# second.net
KiCad netlist of a schematic drawn in EAGLE
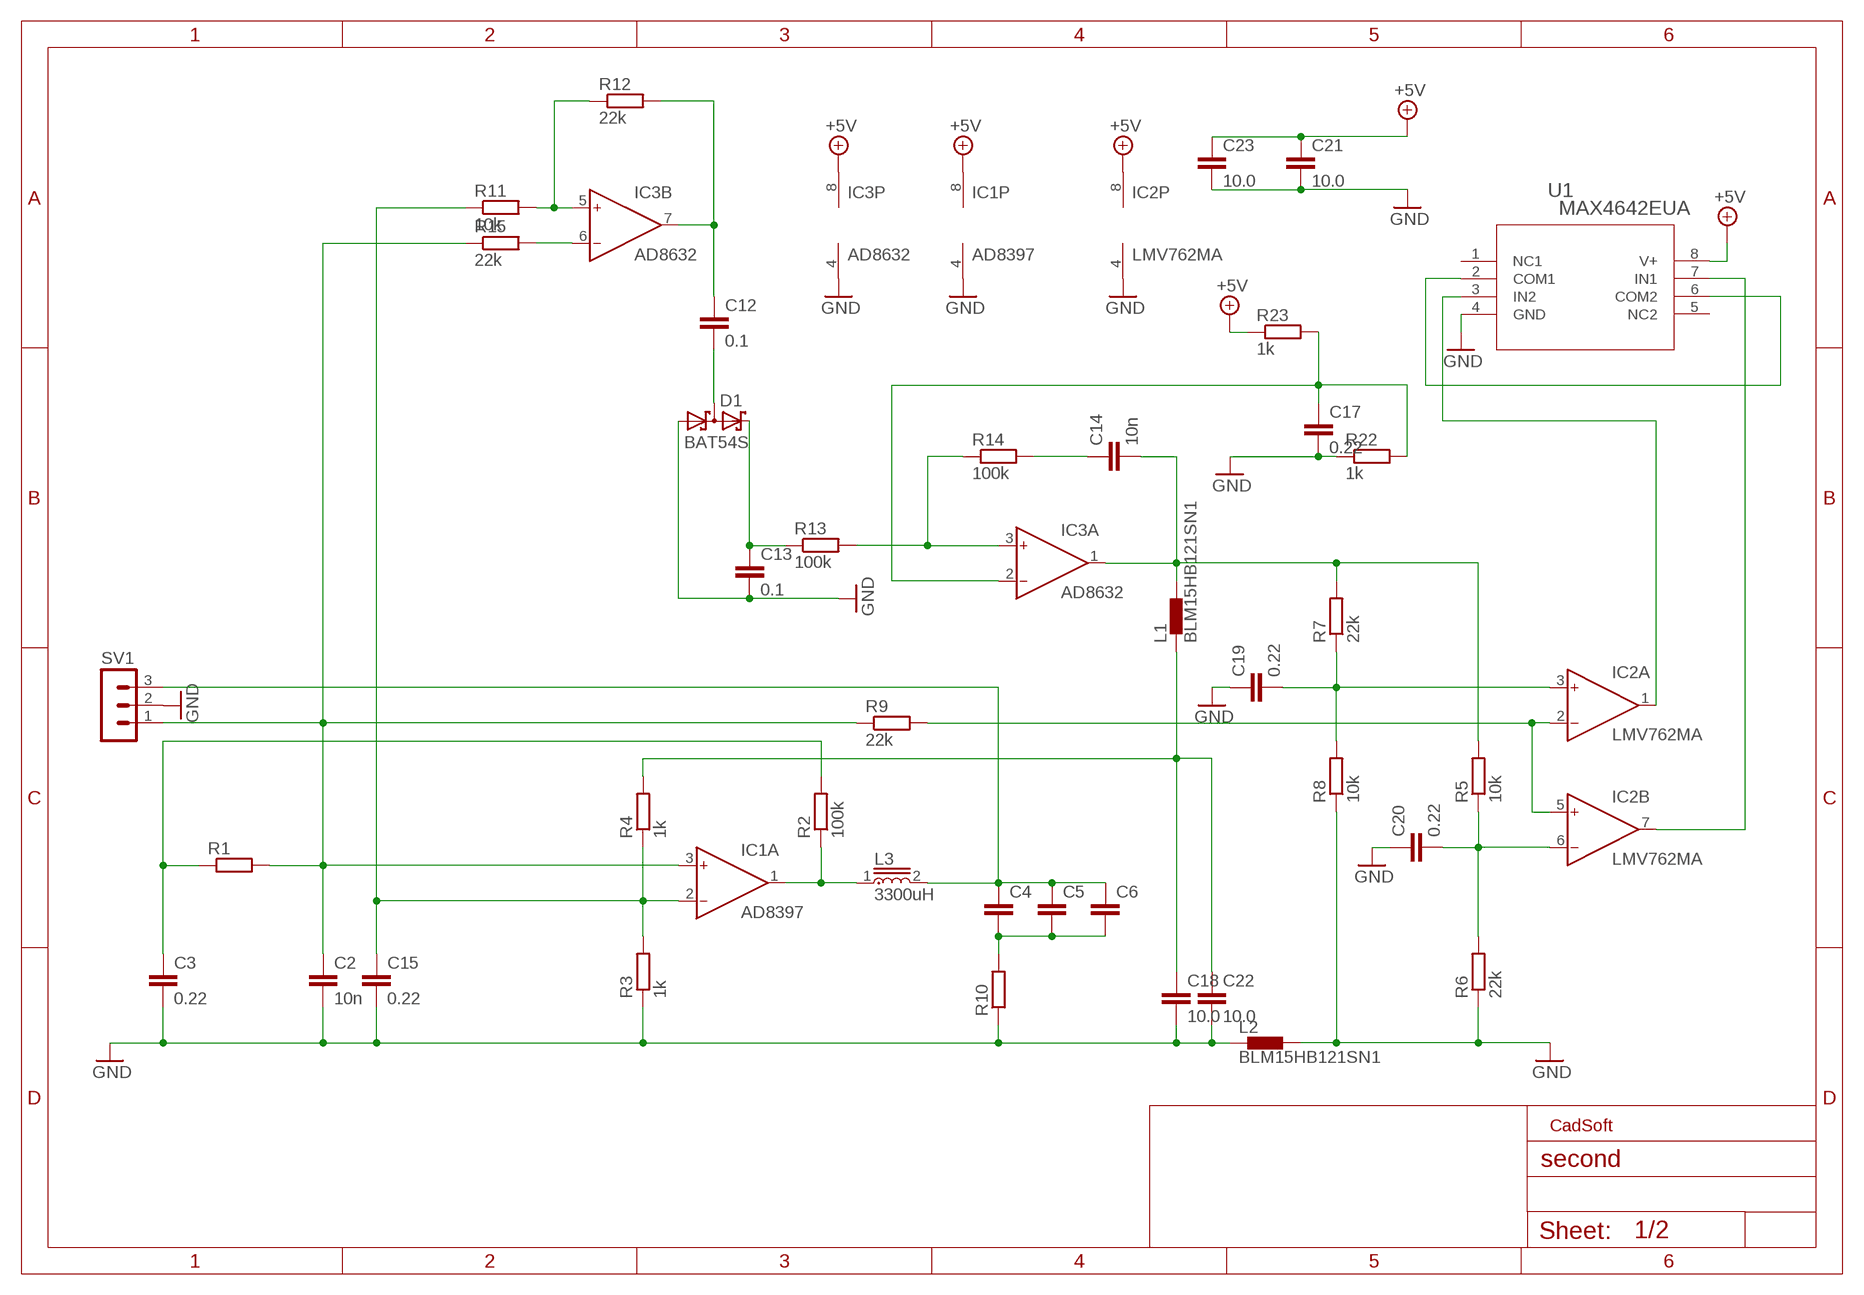
[diagram p0: schematic, sheet 1]
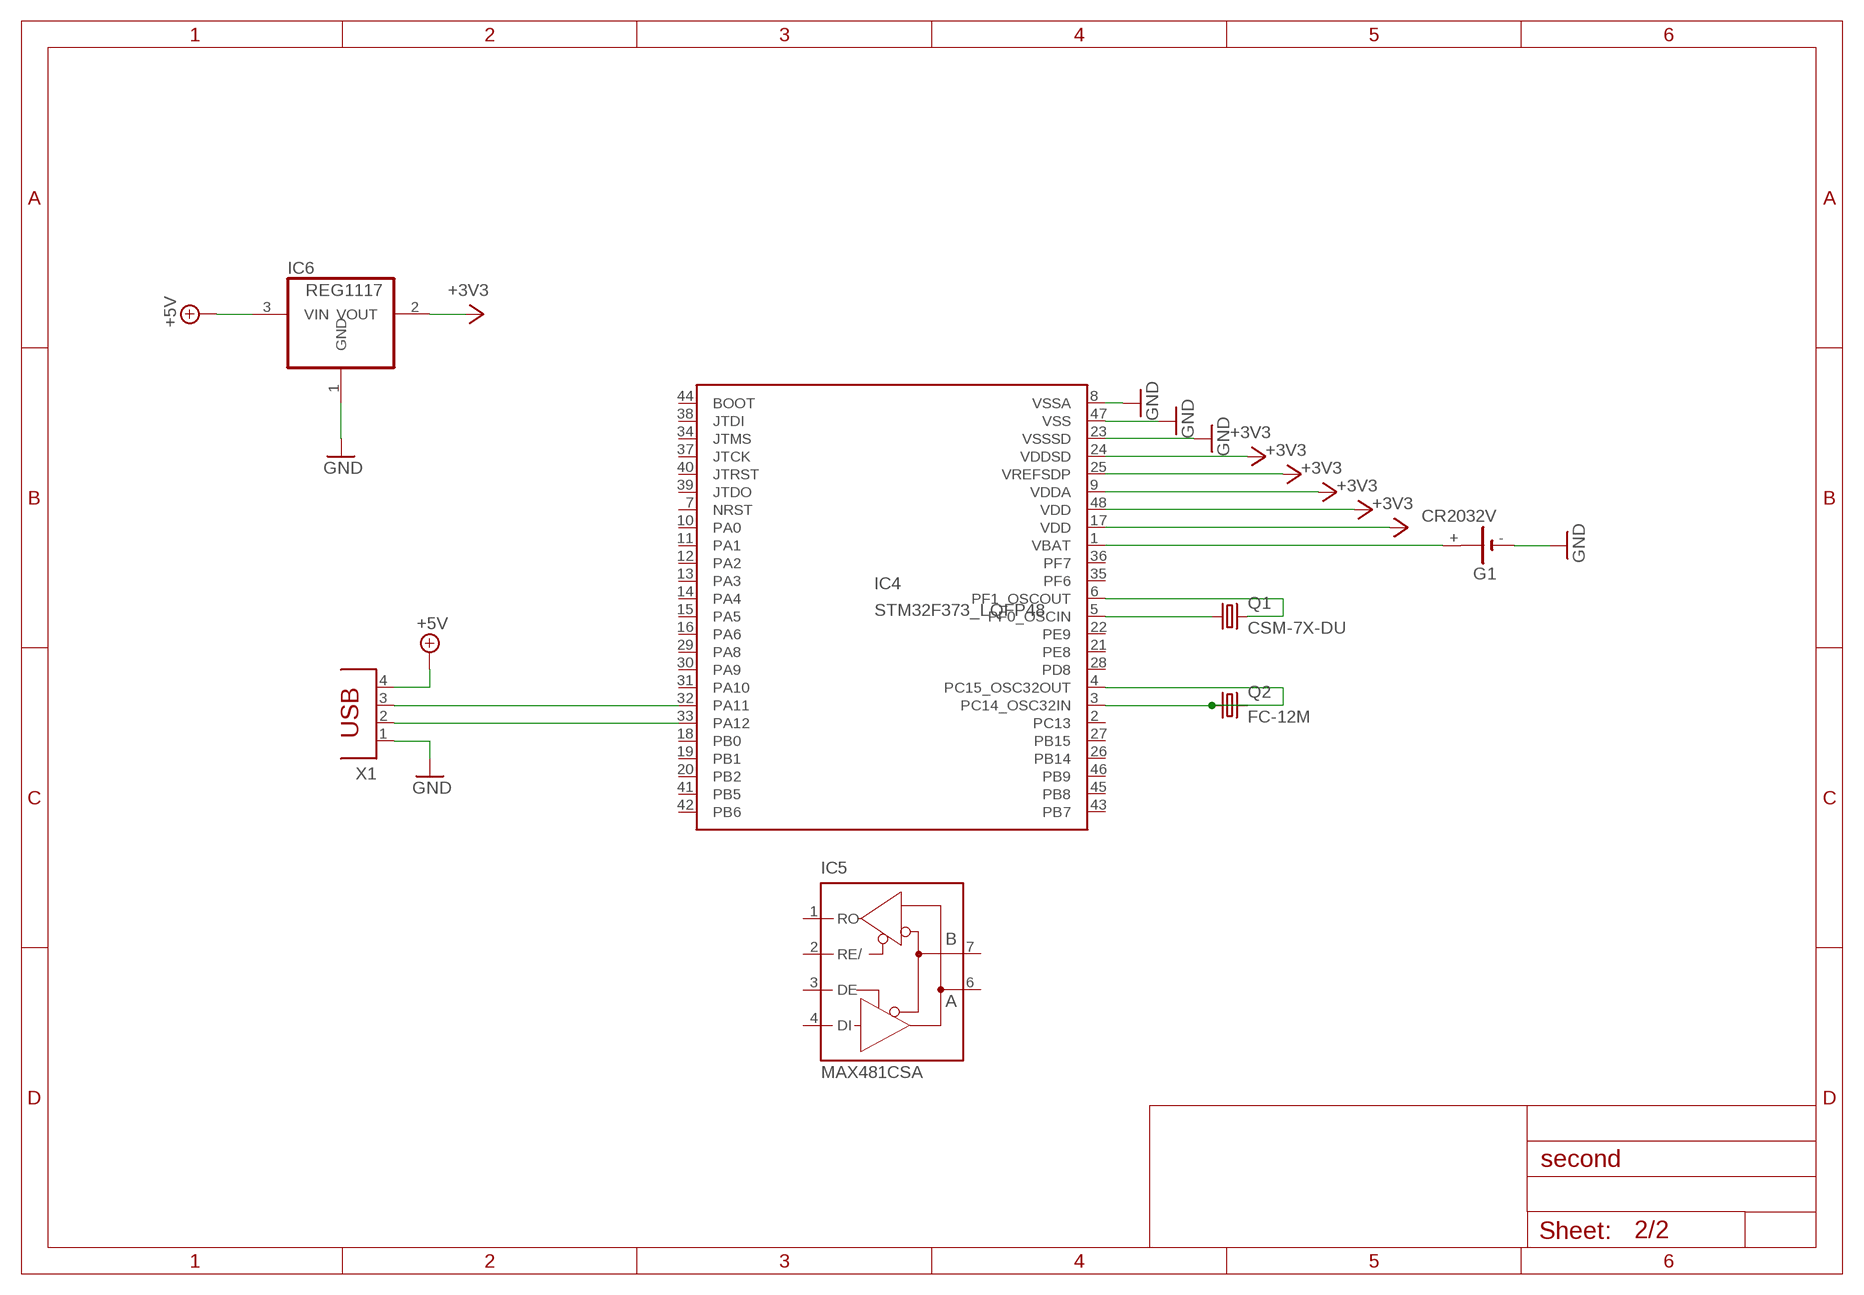
[diagram p1: schematic, sheet 2]

(export (version "E")
  (design (tool "Eeschema 10.0.6"))
  (components
    (comp (ref "C2")
      (value "10n")
      (footprint "eagle-import:C0805")
      (libsource (lib "eagle-import") (part "C-EUC0805"))
    )
    (comp (ref "C3")
      (value "0.22")
      (footprint "eagle-import:C0805")
      (libsource (lib "eagle-import") (part "C-EUC0805"))
    )
    (comp (ref "C4")
      (value "C-EUC0805")
      (footprint "eagle-import:C0805")
      (libsource (lib "eagle-import") (part "C-EUC0805"))
    )
    (comp (ref "C5")
      (value "C-EUC0805")
      (footprint "eagle-import:C0805")
      (libsource (lib "eagle-import") (part "C-EUC0805"))
    )
    (comp (ref "C6")
      (value "C-EUC0805")
      (footprint "eagle-import:C0805")
      (libsource (lib "eagle-import") (part "C-EUC0805"))
    )
    (comp (ref "C12")
      (value "0.1")
      (footprint "eagle-import:C0805")
      (libsource (lib "eagle-import") (part "C-EUC0805"))
    )
    (comp (ref "C13")
      (value "0.1")
      (footprint "eagle-import:C0805")
      (libsource (lib "eagle-import") (part "C-EUC0805"))
    )
    (comp (ref "C14")
      (value "10n")
      (footprint "eagle-import:C0805")
      (libsource (lib "eagle-import") (part "C-EUC0805"))
    )
    (comp (ref "C15")
      (value "0.22")
      (footprint "eagle-import:C0805")
      (libsource (lib "eagle-import") (part "C-EUC0805"))
    )
    (comp (ref "C17")
      (value "0.22")
      (footprint "eagle-import:C0805")
      (libsource (lib "eagle-import") (part "C-EUC0805"))
    )
    (comp (ref "C18")
      (value "10.0")
      (footprint "eagle-import:C0805")
      (libsource (lib "eagle-import") (part "C-EUC0805"))
    )
    (comp (ref "C19")
      (value "0.22")
      (footprint "eagle-import:C0805")
      (libsource (lib "eagle-import") (part "C-EUC0805"))
    )
    (comp (ref "C20")
      (value "0.22")
      (footprint "eagle-import:C0805")
      (libsource (lib "eagle-import") (part "C-EUC0805"))
    )
    (comp (ref "C21")
      (value "10.0")
      (footprint "eagle-import:C0805")
      (libsource (lib "eagle-import") (part "C-EUC0805"))
    )
    (comp (ref "C22")
      (value "10.0")
      (footprint "eagle-import:C0805")
      (libsource (lib "eagle-import") (part "C-EUC0805"))
    )
    (comp (ref "C23")
      (value "10.0")
      (footprint "eagle-import:C0805")
      (libsource (lib "eagle-import") (part "C-EUC0805"))
    )
    (comp (ref "D1")
      (value "BAT54S")
      (footprint "eagle-import:SOT23")
      (libsource (lib "eagle-import") (part "BAT54S"))
    )
    (comp (ref "IC1")
      (value "AD8397")
      (footprint "eagle-import:SO8")
      (fields (field (name "MF") "ANALOG DEVICES") (field (name "MPN") "AD822BRZ"))
      (libsource (lib "eagle-import") (part "AD822R"))
    )
    (comp (ref "IC2")
      (value "LMV762MA")
      (footprint "eagle-import:SO8")
      (fields (field (name "MF") "ANALOG DEVICES") (field (name "MPN") "AD822BRZ"))
      (libsource (lib "eagle-import") (part "AD822R"))
    )
    (comp (ref "IC3")
      (value "AD8632")
      (footprint "eagle-import:SO8")
      (fields (field (name "MF") "ANALOG DEVICES") (field (name "MPN") "AD822BRZ"))
      (libsource (lib "eagle-import") (part "AD822R"))
    )
    (comp (ref "L1")
      (value "BLM15HB121SN1")
      (footprint "eagle-import:0402")
      (libsource (lib "eagle-import") (part "BLM15HB121SN1"))
    )
    (comp (ref "L2")
      (value "BLM15HB121SN1")
      (footprint "eagle-import:0402")
      (libsource (lib "eagle-import") (part "BLM15HB121SN1"))
    )
    (comp (ref "L3")
      (value "3300uH")
      (footprint "eagle-import:P0762NL")
      (libsource (lib "eagle-import") (part "P0762.NL103"))
    )
    (comp (ref "R1")
      (value "R-EU_R0805")
      (footprint "eagle-import:R0805")
      (libsource (lib "eagle-import") (part "R-EU_R0805"))
    )
    (comp (ref "R2")
      (value "100k")
      (footprint "eagle-import:R0805")
      (libsource (lib "eagle-import") (part "R-EU_R0805"))
    )
    (comp (ref "R3")
      (value "1k")
      (footprint "eagle-import:R0805")
      (libsource (lib "eagle-import") (part "R-EU_R0805"))
    )
    (comp (ref "R4")
      (value "1k")
      (footprint "eagle-import:R0805")
      (libsource (lib "eagle-import") (part "R-EU_R0805"))
    )
    (comp (ref "R5")
      (value "10k")
      (footprint "eagle-import:R0805")
      (libsource (lib "eagle-import") (part "R-EU_R0805"))
    )
    (comp (ref "R6")
      (value "22k")
      (footprint "eagle-import:R0805")
      (libsource (lib "eagle-import") (part "R-EU_R0805"))
    )
    (comp (ref "R7")
      (value "22k")
      (footprint "eagle-import:R0805")
      (libsource (lib "eagle-import") (part "R-EU_R0805"))
    )
    (comp (ref "R8")
      (value "10k")
      (footprint "eagle-import:R0805")
      (libsource (lib "eagle-import") (part "R-EU_R0805"))
    )
    (comp (ref "R9")
      (value "22k")
      (footprint "eagle-import:R0805")
      (libsource (lib "eagle-import") (part "R-EU_R0805"))
    )
    (comp (ref "R10")
      (value "R-EU_R0805")
      (footprint "eagle-import:R0805")
      (libsource (lib "eagle-import") (part "R-EU_R0805"))
    )
    (comp (ref "R11")
      (value "10k")
      (footprint "eagle-import:R0805")
      (libsource (lib "eagle-import") (part "R-EU_R0805"))
    )
    (comp (ref "R12")
      (value "22k")
      (footprint "eagle-import:R0805")
      (libsource (lib "eagle-import") (part "R-EU_R0805"))
    )
    (comp (ref "R13")
      (value "100k")
      (footprint "eagle-import:R0805")
      (libsource (lib "eagle-import") (part "R-EU_R0805"))
    )
    (comp (ref "R14")
      (value "100k")
      (footprint "eagle-import:R0805")
      (libsource (lib "eagle-import") (part "R-EU_R0805"))
    )
    (comp (ref "R15")
      (value "22k")
      (footprint "eagle-import:R0805")
      (libsource (lib "eagle-import") (part "R-EU_R0805"))
    )
    (comp (ref "R22")
      (value "1k")
      (footprint "eagle-import:R0805")
      (libsource (lib "eagle-import") (part "R-EU_R0805"))
    )
    (comp (ref "R23")
      (value "1k")
      (footprint "eagle-import:R0805")
      (libsource (lib "eagle-import") (part "R-EU_R0805"))
    )
    (comp (ref "SV1")
      (value "MA03-1")
      (footprint "eagle-import:MA03-1")
      (libsource (lib "eagle-import") (part "MA03-1"))
    )
    (comp (ref "U1")
      (value "MAX4642EUA")
      (footprint "eagle-import:21-0036K")
      (fields (field (name "MANUFACTURER_PART_NUMBER") "max4642eua"))
      (libsource (lib "eagle-import") (part "MAX4642EUA"))
    )
    (comp (ref "G1")
      (value "CR2032V")
      (footprint "eagle-import:CR2032V")
      (libsource (lib "eagle-import") (part "CR2032V"))
    )
    (comp (ref "IC4")
      (value "STM32F373_LQFP48")
      (footprint "eagle-import:LQFP48_PACKAGE")
      (libsource (lib "eagle-import") (part "STM32F373_LQFP48"))
    )
    (comp (ref "IC5")
      (value "MAX481CSA")
      (footprint "eagle-import:SO08")
      (fields (field (name "MF") "MAXIM"))
      (libsource (lib "eagle-import") (part "MAX481CSA"))
    )
    (comp (ref "IC6")
      (value "REG1117")
      (footprint "eagle-import:SOT223")
      (libsource (lib "eagle-import") (part "REG1117"))
    )
    (comp (ref "Q1")
      (value "CSM-7X-DU")
      (footprint "eagle-import:CSM-7X-DU")
      (libsource (lib "eagle-import") (part "CSM-7X-DU"))
    )
    (comp (ref "Q2")
      (value "FC-12M")
      (footprint "eagle-import:FC-12M")
      (libsource (lib "eagle-import") (part "FC-12M"))
    )
    (comp (ref "X1")
      (value "PN61729")
      (footprint "eagle-import:PN61729")
      (libsource (lib "eagle-import") (part "PN61729"))
    )
  )
  (nets
    (net (code "1") (name "+3V3") (class "Default")
      (node (ref "IC4") (pin "17") (pinfunction "VDD_17") (pintype "power_in"))
      (node (ref "IC4") (pin "24") (pinfunction "VDDSD_24") (pintype "power_in"))
      (node (ref "IC4") (pin "25") (pinfunction "VREFSDP_25") (pintype "passive"))
      (node (ref "IC4") (pin "48") (pinfunction "VDD_48") (pintype "power_in"))
      (node (ref "IC4") (pin "9") (pinfunction "VDDA_9") (pintype "power_in"))
      (node (ref "IC6") (pin "2") (pinfunction "VOUT_2") (pintype "output"))
    )
    (net (code "2") (name "+5V") (class "Default")
      (node (ref "C21") (pin "1") (pinfunction "1_1") (pintype "passive"))
      (node (ref "C23") (pin "1") (pinfunction "1_1") (pintype "passive"))
      (node (ref "IC1") (pin "8") (pinfunction "V+_8") (pintype "power_in"))
      (node (ref "IC2") (pin "8") (pinfunction "V+_8") (pintype "power_in"))
      (node (ref "IC3") (pin "8") (pinfunction "V+_8") (pintype "power_in"))
      (node (ref "IC6") (pin "3") (pinfunction "VIN_3") (pintype "input"))
      (node (ref "R23") (pin "1") (pinfunction "1_1") (pintype "passive"))
      (node (ref "U1") (pin "8") (pinfunction "V+_8") (pintype "power_in"))
      (node (ref "X1") (pin "4") (pinfunction "4_4") (pintype "passive"))
    )
    (net (code "3") (name "GND") (class "Default")
      (node (ref "C13") (pin "2") (pinfunction "2_2") (pintype "passive"))
      (node (ref "C15") (pin "2") (pinfunction "2_2") (pintype "passive"))
      (node (ref "C17") (pin "2") (pinfunction "2_2") (pintype "passive"))
      (node (ref "C18") (pin "2") (pinfunction "2_2") (pintype "passive"))
      (node (ref "C19") (pin "1") (pinfunction "1_1") (pintype "passive"))
      (node (ref "C2") (pin "2") (pinfunction "2_2") (pintype "passive"))
      (node (ref "C20") (pin "1") (pinfunction "1_1") (pintype "passive"))
      (node (ref "C21") (pin "2") (pinfunction "2_2") (pintype "passive"))
      (node (ref "C22") (pin "2") (pinfunction "2_2") (pintype "passive"))
      (node (ref "C23") (pin "2") (pinfunction "2_2") (pintype "passive"))
      (node (ref "C3") (pin "2") (pinfunction "2_2") (pintype "passive"))
      (node (ref "D1") (pin "1") (pinfunction "A1_1") (pintype "passive"))
      (node (ref "G1") (pin "-") (pinfunction "-_-") (pintype "passive"))
      (node (ref "IC1") (pin "4") (pinfunction "V-_4") (pintype "power_in"))
      (node (ref "IC2") (pin "4") (pinfunction "V-_4") (pintype "power_in"))
      (node (ref "IC3") (pin "4") (pinfunction "V-_4") (pintype "power_in"))
      (node (ref "IC4") (pin "23") (pinfunction "VSSSD_23") (pintype "power_in"))
      (node (ref "IC4") (pin "47") (pinfunction "VSS_47") (pintype "power_in"))
      (node (ref "IC4") (pin "8") (pinfunction "VSSA_8") (pintype "power_in"))
      (node (ref "IC6") (pin "1") (pinfunction "GND_1") (pintype "power_in"))
      (node (ref "L2") (pin "1") (pinfunction "1_1") (pintype "passive"))
      (node (ref "L2") (pin "2") (pinfunction "2_2") (pintype "passive"))
      (node (ref "R10") (pin "1") (pinfunction "1_1") (pintype "passive"))
      (node (ref "R22") (pin "1") (pinfunction "1_1") (pintype "passive"))
      (node (ref "R3") (pin "1") (pinfunction "1_1") (pintype "passive"))
      (node (ref "R6") (pin "1") (pinfunction "1_1") (pintype "passive"))
      (node (ref "R8") (pin "1") (pinfunction "1_1") (pintype "passive"))
      (node (ref "SV1") (pin "2") (pinfunction "2_2") (pintype "passive"))
      (node (ref "U1") (pin "4") (pinfunction "GND_4") (pintype "power_in"))
      (node (ref "X1") (pin "1") (pinfunction "1_1") (pintype "passive"))
    )
    (net (code "4") (name "Net-(C3-Pad1)") (class "Default")
      (node (ref "C3") (pin "1") (pinfunction "1_1") (pintype "passive"))
      (node (ref "R1") (pin "1") (pinfunction "1_1") (pintype "passive"))
      (node (ref "R2") (pin "2") (pinfunction "2_2") (pintype "passive"))
    )
    (net (code "5") (name "Net-(C4-Pad1)") (class "Default")
      (node (ref "C4") (pin "1") (pinfunction "1_1") (pintype "passive"))
      (node (ref "C5") (pin "1") (pinfunction "1_1") (pintype "passive"))
      (node (ref "C6") (pin "1") (pinfunction "1_1") (pintype "passive"))
      (node (ref "L3") (pin "2") (pinfunction "2_2") (pintype "passive"))
      (node (ref "SV1") (pin "3") (pinfunction "3_3") (pintype "passive"))
    )
    (net (code "6") (name "Net-(C4-Pad2)") (class "Default")
      (node (ref "C4") (pin "2") (pinfunction "2_2") (pintype "passive"))
      (node (ref "C5") (pin "2") (pinfunction "2_2") (pintype "passive"))
      (node (ref "C6") (pin "2") (pinfunction "2_2") (pintype "passive"))
      (node (ref "R10") (pin "2") (pinfunction "2_2") (pintype "passive"))
    )
    (net (code "7") (name "Net-(C14-Pad1)") (class "Default")
      (node (ref "C14") (pin "1") (pinfunction "1_1") (pintype "passive"))
      (node (ref "R14") (pin "2") (pinfunction "2_2") (pintype "passive"))
    )
    (net (code "8") (name "Net-(C18-Pad1)") (class "Default")
      (node (ref "C18") (pin "1") (pinfunction "1_1") (pintype "passive"))
      (node (ref "C22") (pin "1") (pinfunction "1_1") (pintype "passive"))
      (node (ref "L1") (pin "1") (pinfunction "1_1") (pintype "passive"))
      (node (ref "R4") (pin "2") (pinfunction "2_2") (pintype "passive"))
    )
    (net (code "9") (name "Net-(D1-C1A2)") (class "Default")
      (node (ref "C12") (pin "2") (pinfunction "2_2") (pintype "passive"))
      (node (ref "D1") (pin "3") (pinfunction "C1A2_3") (pintype "passive"))
    )
    (net (code "10") (name "Net-(D1-C2)") (class "Default")
      (node (ref "C13") (pin "1") (pinfunction "1_1") (pintype "passive"))
      (node (ref "D1") (pin "2") (pinfunction "C2_2") (pintype "passive"))
      (node (ref "R13") (pin "1") (pinfunction "1_1") (pintype "passive"))
    )
    (net (code "11") (name "Net-(IC1A-IN+)") (class "Default")
      (node (ref "C2") (pin "1") (pinfunction "1_1") (pintype "passive"))
      (node (ref "IC1") (pin "3") (pinfunction "IN+_3") (pintype "input"))
      (node (ref "R1") (pin "2") (pinfunction "2_2") (pintype "passive"))
      (node (ref "R15") (pin "1") (pinfunction "1_1") (pintype "passive"))
      (node (ref "R9") (pin "1") (pinfunction "1_1") (pintype "passive"))
      (node (ref "SV1") (pin "1") (pinfunction "1_1") (pintype "passive"))
    )
    (net (code "12") (name "Net-(IC1A-IN-)") (class "Default")
      (node (ref "C15") (pin "1") (pinfunction "1_1") (pintype "passive"))
      (node (ref "IC1") (pin "2") (pinfunction "IN-_2") (pintype "input"))
      (node (ref "R11") (pin "1") (pinfunction "1_1") (pintype "passive"))
      (node (ref "R3") (pin "2") (pinfunction "2_2") (pintype "passive"))
      (node (ref "R4") (pin "1") (pinfunction "1_1") (pintype "passive"))
    )
    (net (code "13") (name "Net-(IC1A-OUT)") (class "Default")
      (node (ref "IC1") (pin "1") (pinfunction "OUT_1") (pintype "output"))
      (node (ref "L3") (pin "1") (pinfunction "1_1") (pintype "passive"))
      (node (ref "R2") (pin "1") (pinfunction "1_1") (pintype "passive"))
    )
    (net (code "14") (name "Net-(IC2A-IN+)") (class "Default")
      (node (ref "C19") (pin "2") (pinfunction "2_2") (pintype "passive"))
      (node (ref "IC2") (pin "3") (pinfunction "IN+_3") (pintype "input"))
      (node (ref "R7") (pin "1") (pinfunction "1_1") (pintype "passive"))
      (node (ref "R8") (pin "2") (pinfunction "2_2") (pintype "passive"))
    )
    (net (code "15") (name "Net-(IC2A-IN-)") (class "Default")
      (node (ref "IC2") (pin "2") (pinfunction "IN-_2") (pintype "input"))
      (node (ref "IC2") (pin "5") (pinfunction "IN+_5") (pintype "input"))
      (node (ref "R9") (pin "2") (pinfunction "2_2") (pintype "passive"))
    )
    (net (code "16") (name "Net-(IC2A-OUT)") (class "Default")
      (node (ref "IC2") (pin "1") (pinfunction "OUT_1") (pintype "output"))
      (node (ref "U1") (pin "3") (pinfunction "IN2_3") (pintype "input"))
    )
    (net (code "17") (name "Net-(IC2B-IN-)") (class "Default")
      (node (ref "C20") (pin "2") (pinfunction "2_2") (pintype "passive"))
      (node (ref "IC2") (pin "6") (pinfunction "IN-_6") (pintype "input"))
      (node (ref "R5") (pin "1") (pinfunction "1_1") (pintype "passive"))
      (node (ref "R6") (pin "2") (pinfunction "2_2") (pintype "passive"))
    )
    (net (code "18") (name "Net-(IC2B-OUT)") (class "Default")
      (node (ref "IC2") (pin "7") (pinfunction "OUT_7") (pintype "output"))
      (node (ref "U1") (pin "7") (pinfunction "IN1_7") (pintype "input"))
    )
    (net (code "19") (name "Net-(IC3A-IN+)") (class "Default")
      (node (ref "IC3") (pin "3") (pinfunction "IN+_3") (pintype "input"))
      (node (ref "R13") (pin "2") (pinfunction "2_2") (pintype "passive"))
      (node (ref "R14") (pin "1") (pinfunction "1_1") (pintype "passive"))
    )
    (net (code "20") (name "Net-(IC3A-IN-)") (class "Default")
      (node (ref "C17") (pin "1") (pinfunction "1_1") (pintype "passive"))
      (node (ref "IC3") (pin "2") (pinfunction "IN-_2") (pintype "input"))
      (node (ref "R22") (pin "2") (pinfunction "2_2") (pintype "passive"))
      (node (ref "R23") (pin "2") (pinfunction "2_2") (pintype "passive"))
    )
    (net (code "21") (name "Net-(IC3A-OUT)") (class "Default")
      (node (ref "C14") (pin "2") (pinfunction "2_2") (pintype "passive"))
      (node (ref "IC3") (pin "1") (pinfunction "OUT_1") (pintype "output"))
      (node (ref "L1") (pin "2") (pinfunction "2_2") (pintype "passive"))
      (node (ref "R5") (pin "2") (pinfunction "2_2") (pintype "passive"))
      (node (ref "R7") (pin "2") (pinfunction "2_2") (pintype "passive"))
    )
    (net (code "22") (name "Net-(IC3B-IN+)") (class "Default")
      (node (ref "IC3") (pin "5") (pinfunction "IN+_5") (pintype "input"))
      (node (ref "R11") (pin "2") (pinfunction "2_2") (pintype "passive"))
      (node (ref "R12") (pin "1") (pinfunction "1_1") (pintype "passive"))
    )
    (net (code "23") (name "Net-(IC3B-IN-)") (class "Default")
      (node (ref "IC3") (pin "6") (pinfunction "IN-_6") (pintype "input"))
      (node (ref "R15") (pin "2") (pinfunction "2_2") (pintype "passive"))
    )
    (net (code "24") (name "Net-(IC3B-OUT)") (class "Default")
      (node (ref "C12") (pin "1") (pinfunction "1_1") (pintype "passive"))
      (node (ref "IC3") (pin "7") (pinfunction "OUT_7") (pintype "output"))
      (node (ref "R12") (pin "2") (pinfunction "2_2") (pintype "passive"))
    )
    (net (code "25") (name "Net-(IC4-PA11)") (class "Default")
      (node (ref "IC4") (pin "32") (pinfunction "PA11_32") (pintype "bidirectional"))
      (node (ref "X1") (pin "3") (pinfunction "3_3") (pintype "passive"))
    )
    (net (code "26") (name "Net-(IC4-PA12)") (class "Default")
      (node (ref "IC4") (pin "33") (pinfunction "PA12_33") (pintype "bidirectional"))
      (node (ref "X1") (pin "2") (pinfunction "2_2") (pintype "passive"))
    )
    (net (code "27") (name "Net-(IC4-PC14_OSC32IN)") (class "Default")
      (node (ref "IC4") (pin "3") (pinfunction "PC14_OSC32IN_3") (pintype "bidirectional"))
      (node (ref "IC4") (pin "4") (pinfunction "PC15_OSC32OUT_4") (pintype "bidirectional"))
      (node (ref "Q2") (pin "1") (pinfunction "1_1") (pintype "passive"))
    )
    (net (code "28") (name "Net-(IC4-PF0_OSCIN)") (class "Default")
      (node (ref "IC4") (pin "5") (pinfunction "PF0_OSCIN_5") (pintype "bidirectional"))
      (node (ref "Q1") (pin "1") (pinfunction "1_1") (pintype "passive"))
    )
    (net (code "29") (name "Net-(IC4-PF1_OSCOUT)") (class "Default")
      (node (ref "IC4") (pin "6") (pinfunction "PF1_OSCOUT_6") (pintype "bidirectional"))
      (node (ref "Q1") (pin "2") (pinfunction "2_2") (pintype "passive"))
    )
    (net (code "30") (name "Net-(IC4-VBAT)") (class "Default")
      (node (ref "G1") (pin "+") (pinfunction "+_+") (pintype "passive"))
      (node (ref "IC4") (pin "1") (pinfunction "VBAT_1") (pintype "passive"))
    )
    (net (code "31") (name "Net-(U1-COM1)") (class "Default")
      (node (ref "U1") (pin "2") (pinfunction "COM1_2") (pintype "passive"))
      (node (ref "U1") (pin "6") (pinfunction "COM2_6") (pintype "passive"))
    )
    (net (code "32") (name "unconnected-(G1-+-Pad+@1)") (class "Default")
      (node (ref "G1") (pin "+@1") (pinfunction "+_+@1") (pintype "passive"))
    )
    (net (code "33") (name "unconnected-(IC4-BOOT-Pad44)") (class "Default")
      (node (ref "IC4") (pin "44") (pinfunction "BOOT_44") (pintype "input"))
    )
    (net (code "34") (name "unconnected-(IC4-JTCK-Pad37)") (class "Default")
      (node (ref "IC4") (pin "37") (pinfunction "JTCK_37") (pintype "input"))
    )
    (net (code "35") (name "unconnected-(IC4-JTDI-Pad38)") (class "Default")
      (node (ref "IC4") (pin "38") (pinfunction "JTDI_38") (pintype "input"))
    )
    (net (code "36") (name "unconnected-(IC4-JTDO-Pad39)") (class "Default")
      (node (ref "IC4") (pin "39") (pinfunction "JTDO_39") (pintype "output"))
    )
    (net (code "37") (name "unconnected-(IC4-JTMS-Pad34)") (class "Default")
      (node (ref "IC4") (pin "34") (pinfunction "JTMS_34") (pintype "input"))
    )
    (net (code "38") (name "unconnected-(IC4-JTRST-Pad40)") (class "Default")
      (node (ref "IC4") (pin "40") (pinfunction "JTRST_40") (pintype "input"))
    )
    (net (code "39") (name "unconnected-(IC4-NRST-Pad7)") (class "Default")
      (node (ref "IC4") (pin "7") (pinfunction "NRST_7") (pintype "input"))
    )
    (net (code "40") (name "unconnected-(IC4-PA0-Pad10)") (class "Default")
      (node (ref "IC4") (pin "10") (pinfunction "PA0_10") (pintype "bidirectional"))
    )
    (net (code "41") (name "unconnected-(IC4-PA1-Pad11)") (class "Default")
      (node (ref "IC4") (pin "11") (pinfunction "PA1_11") (pintype "bidirectional"))
    )
    (net (code "42") (name "unconnected-(IC4-PA2-Pad12)") (class "Default")
      (node (ref "IC4") (pin "12") (pinfunction "PA2_12") (pintype "bidirectional"))
    )
    (net (code "43") (name "unconnected-(IC4-PA3-Pad13)") (class "Default")
      (node (ref "IC4") (pin "13") (pinfunction "PA3_13") (pintype "bidirectional"))
    )
    (net (code "44") (name "unconnected-(IC4-PA4-Pad14)") (class "Default")
      (node (ref "IC4") (pin "14") (pinfunction "PA4_14") (pintype "bidirectional"))
    )
    (net (code "45") (name "unconnected-(IC4-PA5-Pad15)") (class "Default")
      (node (ref "IC4") (pin "15") (pinfunction "PA5_15") (pintype "bidirectional"))
    )
    (net (code "46") (name "unconnected-(IC4-PA6-Pad16)") (class "Default")
      (node (ref "IC4") (pin "16") (pinfunction "PA6_16") (pintype "bidirectional"))
    )
    (net (code "47") (name "unconnected-(IC4-PA8-Pad29)") (class "Default")
      (node (ref "IC4") (pin "29") (pinfunction "PA8_29") (pintype "bidirectional"))
    )
    (net (code "48") (name "unconnected-(IC4-PA9-Pad30)") (class "Default")
      (node (ref "IC4") (pin "30") (pinfunction "PA9_30") (pintype "bidirectional"))
    )
    (net (code "49") (name "unconnected-(IC4-PA10-Pad31)") (class "Default")
      (node (ref "IC4") (pin "31") (pinfunction "PA10_31") (pintype "bidirectional"))
    )
    (net (code "50") (name "unconnected-(IC4-PB0-Pad18)") (class "Default")
      (node (ref "IC4") (pin "18") (pinfunction "PB0_18") (pintype "bidirectional"))
    )
    (net (code "51") (name "unconnected-(IC4-PB1-Pad19)") (class "Default")
      (node (ref "IC4") (pin "19") (pinfunction "PB1_19") (pintype "bidirectional"))
    )
    (net (code "52") (name "unconnected-(IC4-PB2-Pad20)") (class "Default")
      (node (ref "IC4") (pin "20") (pinfunction "PB2_20") (pintype "bidirectional"))
    )
    (net (code "53") (name "unconnected-(IC4-PB5-Pad41)") (class "Default")
      (node (ref "IC4") (pin "41") (pinfunction "PB5_41") (pintype "bidirectional"))
    )
    (net (code "54") (name "unconnected-(IC4-PB6-Pad42)") (class "Default")
      (node (ref "IC4") (pin "42") (pinfunction "PB6_42") (pintype "bidirectional"))
    )
    (net (code "55") (name "unconnected-(IC4-PB7-Pad43)") (class "Default")
      (node (ref "IC4") (pin "43") (pinfunction "PB7_43") (pintype "bidirectional"))
    )
    (net (code "56") (name "unconnected-(IC4-PB8-Pad45)") (class "Default")
      (node (ref "IC4") (pin "45") (pinfunction "PB8_45") (pintype "bidirectional"))
    )
    (net (code "57") (name "unconnected-(IC4-PB9-Pad46)") (class "Default")
      (node (ref "IC4") (pin "46") (pinfunction "PB9_46") (pintype "bidirectional"))
    )
    (net (code "58") (name "unconnected-(IC4-PB14-Pad26)") (class "Default")
      (node (ref "IC4") (pin "26") (pinfunction "PB14_26") (pintype "bidirectional"))
    )
    (net (code "59") (name "unconnected-(IC4-PB15-Pad27)") (class "Default")
      (node (ref "IC4") (pin "27") (pinfunction "PB15_27") (pintype "bidirectional"))
    )
    (net (code "60") (name "unconnected-(IC4-PC13-Pad2)") (class "Default")
      (node (ref "IC4") (pin "2") (pinfunction "PC13_2") (pintype "bidirectional"))
    )
    (net (code "61") (name "unconnected-(IC4-PD8-Pad28)") (class "Default")
      (node (ref "IC4") (pin "28") (pinfunction "PD8_28") (pintype "bidirectional"))
    )
    (net (code "62") (name "unconnected-(IC4-PE8-Pad21)") (class "Default")
      (node (ref "IC4") (pin "21") (pinfunction "PE8_21") (pintype "bidirectional"))
    )
    (net (code "63") (name "unconnected-(IC4-PE9-Pad22)") (class "Default")
      (node (ref "IC4") (pin "22") (pinfunction "PE9_22") (pintype "bidirectional"))
    )
    (net (code "64") (name "unconnected-(IC4-PF6-Pad35)") (class "Default")
      (node (ref "IC4") (pin "35") (pinfunction "PF6_35") (pintype "bidirectional"))
    )
    (net (code "65") (name "unconnected-(IC4-PF7-Pad36)") (class "Default")
      (node (ref "IC4") (pin "36") (pinfunction "PF7_36") (pintype "bidirectional"))
    )
    (net (code "66") (name "unconnected-(IC5A-A-Pad6)") (class "Default")
      (node (ref "IC5") (pin "6") (pinfunction "A_6") (pintype "passive"))
    )
    (net (code "67") (name "unconnected-(IC5A-B-Pad7)") (class "Default")
      (node (ref "IC5") (pin "7") (pinfunction "B_7") (pintype "passive"))
    )
    (net (code "68") (name "unconnected-(IC5A-DE-Pad3)") (class "Default")
      (node (ref "IC5") (pin "3") (pinfunction "DE_3") (pintype "input"))
    )
    (net (code "69") (name "unconnected-(IC5A-DI-Pad4)") (class "Default")
      (node (ref "IC5") (pin "4") (pinfunction "DI_4") (pintype "input"))
    )
    (net (code "70") (name "unconnected-(IC5A-RE{slash}-Pad2)") (class "Default")
      (node (ref "IC5") (pin "2") (pinfunction "RE/_2") (pintype "input"))
    )
    (net (code "71") (name "unconnected-(IC5A-RO-Pad1)") (class "Default")
      (node (ref "IC5") (pin "1") (pinfunction "RO_1") (pintype "output"))
    )
    (net (code "72") (name "unconnected-(Q2-Pad2)") (class "Default")
      (node (ref "Q2") (pin "2") (pinfunction "2_2") (pintype "passive"))
    )
    (net (code "73") (name "unconnected-(U1-NC1-Pad1)") (class "Default")
      (node (ref "U1") (pin "1") (pinfunction "NC1_1") (pintype "passive"))
    )
    (net (code "74") (name "unconnected-(U1-NC2-Pad5)") (class "Default")
      (node (ref "U1") (pin "5") (pinfunction "NC2_5") (pintype "passive"))
    )
  )
)
